# R284X.net
KiCad netlist of a schematic drawn in EAGLE
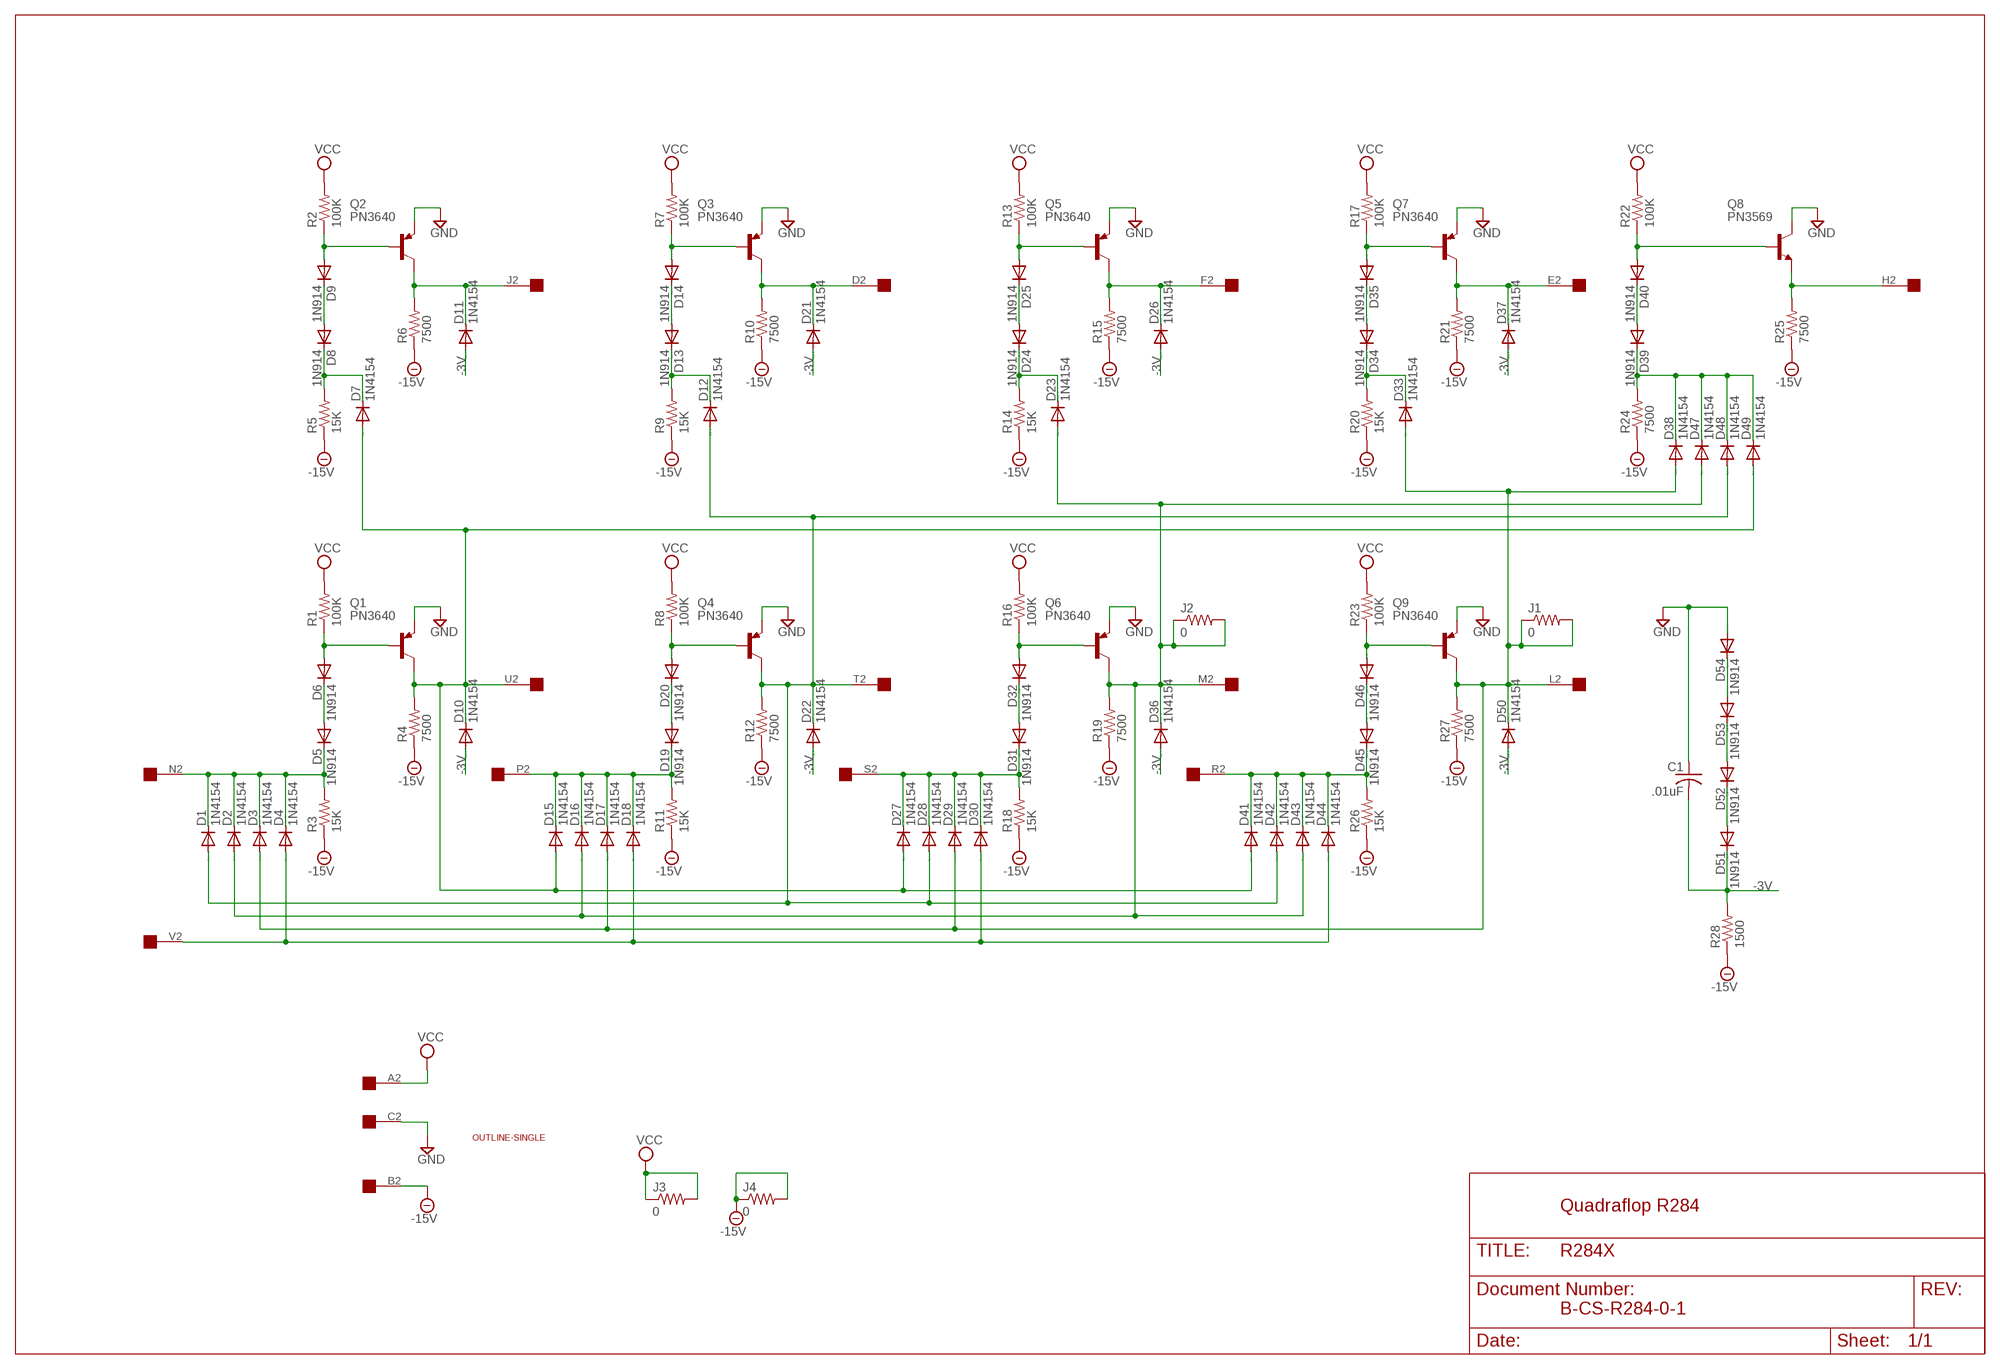
[diagram p0: schematic, sheet 1]

(export (version "E")
  (design (tool "Eeschema 10.0.6"))
  (components
    (comp (ref "C1")
      (value ".01uF")
      (footprint "eagle-import:C063-025X075")
      (libsource (lib "eagle-import") (part "C-US"))
    )
    (comp (ref "D1")
      (value "1N4154")
      (footprint "eagle-import:DO35-10")
      (libsource (lib "eagle-import") (part "DIODE-DO35-10"))
    )
    (comp (ref "D2")
      (value "1N4154")
      (footprint "eagle-import:DO35-10")
      (libsource (lib "eagle-import") (part "DIODE-DO35-10"))
    )
    (comp (ref "D3")
      (value "1N4154")
      (footprint "eagle-import:DO35-10")
      (libsource (lib "eagle-import") (part "DIODE-DO35-10"))
    )
    (comp (ref "D4")
      (value "1N4154")
      (footprint "eagle-import:DO35-10")
      (libsource (lib "eagle-import") (part "DIODE-DO35-10"))
    )
    (comp (ref "D5")
      (value "1N914")
      (footprint "eagle-import:DO35-10")
      (libsource (lib "eagle-import") (part "DIODE-DO35-10"))
    )
    (comp (ref "D6")
      (value "1N914")
      (footprint "eagle-import:DO35-10")
      (libsource (lib "eagle-import") (part "DIODE-DO35-10"))
    )
    (comp (ref "D7")
      (value "1N4154")
      (footprint "eagle-import:DO35-10")
      (libsource (lib "eagle-import") (part "DIODE-DO35-10"))
    )
    (comp (ref "D8")
      (value "1N914")
      (footprint "eagle-import:DO35-10")
      (libsource (lib "eagle-import") (part "DIODE-DO35-10"))
    )
    (comp (ref "D9")
      (value "1N914")
      (footprint "eagle-import:DO35-10")
      (libsource (lib "eagle-import") (part "DIODE-DO35-10"))
    )
    (comp (ref "D10")
      (value "1N4154")
      (footprint "eagle-import:DO35-10")
      (libsource (lib "eagle-import") (part "DIODE-DO35-10"))
    )
    (comp (ref "D11")
      (value "1N4154")
      (footprint "eagle-import:DO35-10")
      (libsource (lib "eagle-import") (part "DIODE-DO35-10"))
    )
    (comp (ref "D12")
      (value "1N4154")
      (footprint "eagle-import:DO35-10")
      (libsource (lib "eagle-import") (part "DIODE-DO35-10"))
    )
    (comp (ref "D13")
      (value "1N914")
      (footprint "eagle-import:DO35-10")
      (libsource (lib "eagle-import") (part "DIODE-DO35-10"))
    )
    (comp (ref "D14")
      (value "1N914")
      (footprint "eagle-import:DO35-10")
      (libsource (lib "eagle-import") (part "DIODE-DO35-10"))
    )
    (comp (ref "D15")
      (value "1N4154")
      (footprint "eagle-import:DO35-10")
      (libsource (lib "eagle-import") (part "DIODE-DO35-10"))
    )
    (comp (ref "D16")
      (value "1N4154")
      (footprint "eagle-import:DO35-10")
      (libsource (lib "eagle-import") (part "DIODE-DO35-10"))
    )
    (comp (ref "D17")
      (value "1N4154")
      (footprint "eagle-import:DO35-10")
      (libsource (lib "eagle-import") (part "DIODE-DO35-10"))
    )
    (comp (ref "D18")
      (value "1N4154")
      (footprint "eagle-import:DO35-10")
      (libsource (lib "eagle-import") (part "DIODE-DO35-10"))
    )
    (comp (ref "D19")
      (value "1N914")
      (footprint "eagle-import:DO35-10")
      (libsource (lib "eagle-import") (part "DIODE-DO35-10"))
    )
    (comp (ref "D20")
      (value "1N914")
      (footprint "eagle-import:DO35-10")
      (libsource (lib "eagle-import") (part "DIODE-DO35-10"))
    )
    (comp (ref "D21")
      (value "1N4154")
      (footprint "eagle-import:DO35-10")
      (libsource (lib "eagle-import") (part "DIODE-DO35-10"))
    )
    (comp (ref "D22")
      (value "1N4154")
      (footprint "eagle-import:DO35-10")
      (libsource (lib "eagle-import") (part "DIODE-DO35-10"))
    )
    (comp (ref "D23")
      (value "1N4154")
      (footprint "eagle-import:DO35-10")
      (libsource (lib "eagle-import") (part "DIODE-DO35-10"))
    )
    (comp (ref "D24")
      (value "1N914")
      (footprint "eagle-import:DO35-10")
      (libsource (lib "eagle-import") (part "DIODE-DO35-10"))
    )
    (comp (ref "D25")
      (value "1N914")
      (footprint "eagle-import:DO35-10")
      (libsource (lib "eagle-import") (part "DIODE-DO35-10"))
    )
    (comp (ref "D26")
      (value "1N4154")
      (footprint "eagle-import:DO35-10")
      (libsource (lib "eagle-import") (part "DIODE-DO35-10"))
    )
    (comp (ref "D27")
      (value "1N4154")
      (footprint "eagle-import:DO35-10")
      (libsource (lib "eagle-import") (part "DIODE-DO35-10"))
    )
    (comp (ref "D28")
      (value "1N4154")
      (footprint "eagle-import:DO35-10")
      (libsource (lib "eagle-import") (part "DIODE-DO35-10"))
    )
    (comp (ref "D29")
      (value "1N4154")
      (footprint "eagle-import:DO35-10")
      (libsource (lib "eagle-import") (part "DIODE-DO35-10"))
    )
    (comp (ref "D30")
      (value "1N4154")
      (footprint "eagle-import:DO35-10")
      (libsource (lib "eagle-import") (part "DIODE-DO35-10"))
    )
    (comp (ref "D31")
      (value "1N914")
      (footprint "eagle-import:DO35-10")
      (libsource (lib "eagle-import") (part "DIODE-DO35-10"))
    )
    (comp (ref "D32")
      (value "1N914")
      (footprint "eagle-import:DO35-10")
      (libsource (lib "eagle-import") (part "DIODE-DO35-10"))
    )
    (comp (ref "D33")
      (value "1N4154")
      (footprint "eagle-import:DO35-10")
      (libsource (lib "eagle-import") (part "DIODE-DO35-10"))
    )
    (comp (ref "D34")
      (value "1N914")
      (footprint "eagle-import:DO35-10")
      (libsource (lib "eagle-import") (part "DIODE-DO35-10"))
    )
    (comp (ref "D35")
      (value "1N914")
      (footprint "eagle-import:DO35-10")
      (libsource (lib "eagle-import") (part "DIODE-DO35-10"))
    )
    (comp (ref "D36")
      (value "1N4154")
      (footprint "eagle-import:DO35-10")
      (libsource (lib "eagle-import") (part "DIODE-DO35-10"))
    )
    (comp (ref "D37")
      (value "1N4154")
      (footprint "eagle-import:DO35-10")
      (libsource (lib "eagle-import") (part "DIODE-DO35-10"))
    )
    (comp (ref "D38")
      (value "1N4154")
      (footprint "eagle-import:DO35-10")
      (libsource (lib "eagle-import") (part "DIODE-DO35-10"))
    )
    (comp (ref "D39")
      (value "1N914")
      (footprint "eagle-import:DO35-10")
      (libsource (lib "eagle-import") (part "DIODE-DO35-10"))
    )
    (comp (ref "D40")
      (value "1N914")
      (footprint "eagle-import:DO35-10")
      (libsource (lib "eagle-import") (part "DIODE-DO35-10"))
    )
    (comp (ref "D41")
      (value "1N4154")
      (footprint "eagle-import:DO35-10")
      (libsource (lib "eagle-import") (part "DIODE-DO35-10"))
    )
    (comp (ref "D42")
      (value "1N4154")
      (footprint "eagle-import:DO35-10")
      (libsource (lib "eagle-import") (part "DIODE-DO35-10"))
    )
    (comp (ref "D43")
      (value "1N4154")
      (footprint "eagle-import:DO35-10")
      (libsource (lib "eagle-import") (part "DIODE-DO35-10"))
    )
    (comp (ref "D44")
      (value "1N4154")
      (footprint "eagle-import:DO35-10")
      (libsource (lib "eagle-import") (part "DIODE-DO35-10"))
    )
    (comp (ref "D45")
      (value "1N914")
      (footprint "eagle-import:DO35-10")
      (libsource (lib "eagle-import") (part "DIODE-DO35-10"))
    )
    (comp (ref "D46")
      (value "1N914")
      (footprint "eagle-import:DO35-10")
      (libsource (lib "eagle-import") (part "DIODE-DO35-10"))
    )
    (comp (ref "D47")
      (value "1N4154")
      (footprint "eagle-import:DO35-10")
      (libsource (lib "eagle-import") (part "DIODE-DO35-10"))
    )
    (comp (ref "D48")
      (value "1N4154")
      (footprint "eagle-import:DO35-10")
      (libsource (lib "eagle-import") (part "DIODE-DO35-10"))
    )
    (comp (ref "D49")
      (value "1N4154")
      (footprint "eagle-import:DO35-10")
      (libsource (lib "eagle-import") (part "DIODE-DO35-10"))
    )
    (comp (ref "D50")
      (value "1N4154")
      (footprint "eagle-import:DO35-10")
      (libsource (lib "eagle-import") (part "DIODE-DO35-10"))
    )
    (comp (ref "D51")
      (value "1N914")
      (footprint "eagle-import:DO35-10")
      (libsource (lib "eagle-import") (part "DIODE-DO35-10"))
    )
    (comp (ref "D52")
      (value "1N914")
      (footprint "eagle-import:DO35-10")
      (libsource (lib "eagle-import") (part "DIODE-DO35-10"))
    )
    (comp (ref "D53")
      (value "1N914")
      (footprint "eagle-import:DO35-10")
      (libsource (lib "eagle-import") (part "DIODE-DO35-10"))
    )
    (comp (ref "D54")
      (value "1N914")
      (footprint "eagle-import:DO35-10")
      (libsource (lib "eagle-import") (part "DIODE-DO35-10"))
    )
    (comp (ref "J1")
      (value "0")
      (footprint "eagle-import:0207_10")
      (libsource (lib "eagle-import") (part "R-US_0207/10"))
    )
    (comp (ref "J2")
      (value "0")
      (footprint "eagle-import:0207_10")
      (libsource (lib "eagle-import") (part "R-US_0207/10"))
    )
    (comp (ref "J3")
      (value "0")
      (footprint "eagle-import:0207_10")
      (libsource (lib "eagle-import") (part "R-US_0207/10"))
    )
    (comp (ref "J4")
      (value "0")
      (footprint "eagle-import:0207_10")
      (libsource (lib "eagle-import") (part "R-US_0207/10"))
    )
    (comp (ref "Q1")
      (value "PN3640")
      (footprint "eagle-import:TO5")
      (libsource (lib "eagle-import") (part "-PNP-TO5"))
    )
    (comp (ref "Q2")
      (value "PN3640")
      (footprint "eagle-import:TO5")
      (libsource (lib "eagle-import") (part "-PNP-TO5"))
    )
    (comp (ref "Q3")
      (value "PN3640")
      (footprint "eagle-import:TO5")
      (libsource (lib "eagle-import") (part "-PNP-TO5"))
    )
    (comp (ref "Q4")
      (value "PN3640")
      (footprint "eagle-import:TO5")
      (libsource (lib "eagle-import") (part "-PNP-TO5"))
    )
    (comp (ref "Q5")
      (value "PN3640")
      (footprint "eagle-import:TO5")
      (libsource (lib "eagle-import") (part "-PNP-TO5"))
    )
    (comp (ref "Q6")
      (value "PN3640")
      (footprint "eagle-import:TO5")
      (libsource (lib "eagle-import") (part "-PNP-TO5"))
    )
    (comp (ref "Q7")
      (value "PN3640")
      (footprint "eagle-import:TO5")
      (libsource (lib "eagle-import") (part "-PNP-TO5"))
    )
    (comp (ref "Q8")
      (value "PN3569")
      (footprint "eagle-import:TO5")
      (libsource (lib "eagle-import") (part "-NPN-TO5"))
    )
    (comp (ref "Q9")
      (value "PN3640")
      (footprint "eagle-import:TO5")
      (libsource (lib "eagle-import") (part "-PNP-TO5"))
    )
    (comp (ref "R1")
      (value "100K")
      (footprint "eagle-import:0207_10")
      (libsource (lib "eagle-import") (part "R-US_0207/10"))
    )
    (comp (ref "R2")
      (value "100K")
      (footprint "eagle-import:0207_10")
      (libsource (lib "eagle-import") (part "R-US_0207/10"))
    )
    (comp (ref "R3")
      (value "15K")
      (footprint "eagle-import:0207_10")
      (libsource (lib "eagle-import") (part "R-US_0207/10"))
    )
    (comp (ref "R4")
      (value "7500")
      (footprint "eagle-import:0207_10")
      (libsource (lib "eagle-import") (part "R-US_0207/10"))
    )
    (comp (ref "R5")
      (value "15K")
      (footprint "eagle-import:0207_10")
      (libsource (lib "eagle-import") (part "R-US_0207/10"))
    )
    (comp (ref "R6")
      (value "7500")
      (footprint "eagle-import:0207_10")
      (libsource (lib "eagle-import") (part "R-US_0207/10"))
    )
    (comp (ref "R7")
      (value "100K")
      (footprint "eagle-import:0207_10")
      (libsource (lib "eagle-import") (part "R-US_0207/10"))
    )
    (comp (ref "R8")
      (value "100K")
      (footprint "eagle-import:0207_10")
      (libsource (lib "eagle-import") (part "R-US_0207/10"))
    )
    (comp (ref "R9")
      (value "15K")
      (footprint "eagle-import:0207_10")
      (libsource (lib "eagle-import") (part "R-US_0207/10"))
    )
    (comp (ref "R10")
      (value "7500")
      (footprint "eagle-import:0207_10")
      (libsource (lib "eagle-import") (part "R-US_0207/10"))
    )
    (comp (ref "R11")
      (value "15K")
      (footprint "eagle-import:0207_10")
      (libsource (lib "eagle-import") (part "R-US_0207/10"))
    )
    (comp (ref "R12")
      (value "7500")
      (footprint "eagle-import:0207_10")
      (libsource (lib "eagle-import") (part "R-US_0207/10"))
    )
    (comp (ref "R13")
      (value "100K")
      (footprint "eagle-import:0207_10")
      (libsource (lib "eagle-import") (part "R-US_0207/10"))
    )
    (comp (ref "R14")
      (value "15K")
      (footprint "eagle-import:0207_10")
      (libsource (lib "eagle-import") (part "R-US_0207/10"))
    )
    (comp (ref "R15")
      (value "7500")
      (footprint "eagle-import:0207_10")
      (libsource (lib "eagle-import") (part "R-US_0207/10"))
    )
    (comp (ref "R16")
      (value "100K")
      (footprint "eagle-import:0207_10")
      (libsource (lib "eagle-import") (part "R-US_0207/10"))
    )
    (comp (ref "R17")
      (value "100K")
      (footprint "eagle-import:0207_10")
      (libsource (lib "eagle-import") (part "R-US_0207/10"))
    )
    (comp (ref "R18")
      (value "15K")
      (footprint "eagle-import:0207_10")
      (libsource (lib "eagle-import") (part "R-US_0207/10"))
    )
    (comp (ref "R19")
      (value "7500")
      (footprint "eagle-import:0207_10")
      (libsource (lib "eagle-import") (part "R-US_0207/10"))
    )
    (comp (ref "R20")
      (value "15K")
      (footprint "eagle-import:0207_10")
      (libsource (lib "eagle-import") (part "R-US_0207/10"))
    )
    (comp (ref "R21")
      (value "7500")
      (footprint "eagle-import:0207_10")
      (libsource (lib "eagle-import") (part "R-US_0207/10"))
    )
    (comp (ref "R22")
      (value "100K")
      (footprint "eagle-import:0207_10")
      (libsource (lib "eagle-import") (part "R-US_0207/10"))
    )
    (comp (ref "R23")
      (value "100K")
      (footprint "eagle-import:0207_10")
      (libsource (lib "eagle-import") (part "R-US_0207/10"))
    )
    (comp (ref "R24")
      (value "7500")
      (footprint "eagle-import:0207_10")
      (libsource (lib "eagle-import") (part "R-US_0207/10"))
    )
    (comp (ref "R25")
      (value "7500")
      (footprint "eagle-import:0207_10")
      (libsource (lib "eagle-import") (part "R-US_0207/10"))
    )
    (comp (ref "R26")
      (value "15K")
      (footprint "eagle-import:0207_10")
      (libsource (lib "eagle-import") (part "R-US_0207/10"))
    )
    (comp (ref "R27")
      (value "7500")
      (footprint "eagle-import:0207_10")
      (libsource (lib "eagle-import") (part "R-US_0207/10"))
    )
    (comp (ref "R28")
      (value "1500")
      (footprint "eagle-import:0207_10")
      (libsource (lib "eagle-import") (part "R-US_0207/10"))
    )
    (comp (ref "U$1")
      (value "OUTLINE-SINGLE")
      (footprint "eagle-import:SINGLE")
      (libsource (lib "eagle-import") (part "OUTLINE-SINGLE"))
    )
    (comp (ref "U$2")
      (value "EDGE-1")
      (footprint "eagle-import:EDGE-CON1")
      (libsource (lib "eagle-import") (part "EDGE-1"))
    )
  )
  (nets
    (net (code "1") (name "-15V") (class "Default")
      (node (ref "J4") (pin "1") (pinfunction "1_1") (pintype "passive"))
      (node (ref "J4") (pin "2") (pinfunction "2_2") (pintype "passive"))
      (node (ref "R10") (pin "1") (pinfunction "1_1") (pintype "passive"))
      (node (ref "R11") (pin "1") (pinfunction "1_1") (pintype "passive"))
      (node (ref "R12") (pin "1") (pinfunction "1_1") (pintype "passive"))
      (node (ref "R14") (pin "1") (pinfunction "1_1") (pintype "passive"))
      (node (ref "R15") (pin "1") (pinfunction "1_1") (pintype "passive"))
      (node (ref "R18") (pin "1") (pinfunction "1_1") (pintype "passive"))
      (node (ref "R19") (pin "1") (pinfunction "1_1") (pintype "passive"))
      (node (ref "R20") (pin "1") (pinfunction "1_1") (pintype "passive"))
      (node (ref "R21") (pin "1") (pinfunction "1_1") (pintype "passive"))
      (node (ref "R24") (pin "1") (pinfunction "1_1") (pintype "passive"))
      (node (ref "R25") (pin "1") (pinfunction "1_1") (pintype "passive"))
      (node (ref "R26") (pin "1") (pinfunction "1_1") (pintype "passive"))
      (node (ref "R27") (pin "1") (pinfunction "1_1") (pintype "passive"))
      (node (ref "R28") (pin "1") (pinfunction "1_1") (pintype "passive"))
      (node (ref "R3") (pin "1") (pinfunction "1_1") (pintype "passive"))
      (node (ref "R4") (pin "1") (pinfunction "1_1") (pintype "passive"))
      (node (ref "R5") (pin "1") (pinfunction "1_1") (pintype "passive"))
      (node (ref "R6") (pin "1") (pinfunction "1_1") (pintype "passive"))
      (node (ref "R9") (pin "1") (pinfunction "1_1") (pintype "passive"))
      (node (ref "U$2") (pin "B2") (pinfunction "1_B2") (pintype "bidirectional"))
    )
    (net (code "2") (name "/-3V") (class "Default")
      (node (ref "C1") (pin "2") (pinfunction "2_2") (pintype "passive"))
      (node (ref "D10") (pin "A") (pinfunction "A_A") (pintype "passive"))
      (node (ref "D11") (pin "A") (pinfunction "A_A") (pintype "passive"))
      (node (ref "D21") (pin "A") (pinfunction "A_A") (pintype "passive"))
      (node (ref "D22") (pin "A") (pinfunction "A_A") (pintype "passive"))
      (node (ref "D26") (pin "A") (pinfunction "A_A") (pintype "passive"))
      (node (ref "D36") (pin "A") (pinfunction "A_A") (pintype "passive"))
      (node (ref "D37") (pin "A") (pinfunction "A_A") (pintype "passive"))
      (node (ref "D50") (pin "A") (pinfunction "A_A") (pintype "passive"))
      (node (ref "D51") (pin "C") (pinfunction "C_C") (pintype "passive"))
      (node (ref "R28") (pin "2") (pinfunction "2_2") (pintype "passive"))
    )
    (net (code "3") (name "GND") (class "Default")
      (node (ref "C1") (pin "1") (pinfunction "1_1") (pintype "passive"))
      (node (ref "D54") (pin "A") (pinfunction "A_A") (pintype "passive"))
      (node (ref "Q1") (pin "1") (pinfunction "E_1") (pintype "passive"))
      (node (ref "Q2") (pin "1") (pinfunction "E_1") (pintype "passive"))
      (node (ref "Q3") (pin "1") (pinfunction "E_1") (pintype "passive"))
      (node (ref "Q4") (pin "1") (pinfunction "E_1") (pintype "passive"))
      (node (ref "Q5") (pin "1") (pinfunction "E_1") (pintype "passive"))
      (node (ref "Q6") (pin "1") (pinfunction "E_1") (pintype "passive"))
      (node (ref "Q7") (pin "1") (pinfunction "E_1") (pintype "passive"))
      (node (ref "Q8") (pin "3") (pinfunction "C_3") (pintype "passive"))
      (node (ref "Q9") (pin "1") (pinfunction "E_1") (pintype "passive"))
      (node (ref "U$2") (pin "C2") (pinfunction "1_C2") (pintype "bidirectional"))
    )
    (net (code "4") (name "Net-(D5-PadA)") (class "Default")
      (node (ref "D5") (pin "A") (pinfunction "A_A") (pintype "passive"))
      (node (ref "D6") (pin "C") (pinfunction "C_C") (pintype "passive"))
    )
    (net (code "5") (name "Net-(D7-PadC)") (class "Default")
      (node (ref "D7") (pin "C") (pinfunction "C_C") (pintype "passive"))
      (node (ref "D8") (pin "C") (pinfunction "C_C") (pintype "passive"))
      (node (ref "R5") (pin "2") (pinfunction "2_2") (pintype "passive"))
    )
    (net (code "6") (name "Net-(D8-PadA)") (class "Default")
      (node (ref "D8") (pin "A") (pinfunction "A_A") (pintype "passive"))
      (node (ref "D9") (pin "C") (pinfunction "C_C") (pintype "passive"))
    )
    (net (code "7") (name "Net-(D12-PadC)") (class "Default")
      (node (ref "D12") (pin "C") (pinfunction "C_C") (pintype "passive"))
      (node (ref "D13") (pin "C") (pinfunction "C_C") (pintype "passive"))
      (node (ref "R9") (pin "2") (pinfunction "2_2") (pintype "passive"))
    )
    (net (code "8") (name "Net-(D13-PadA)") (class "Default")
      (node (ref "D13") (pin "A") (pinfunction "A_A") (pintype "passive"))
      (node (ref "D14") (pin "C") (pinfunction "C_C") (pintype "passive"))
    )
    (net (code "9") (name "Net-(D19-PadA)") (class "Default")
      (node (ref "D19") (pin "A") (pinfunction "A_A") (pintype "passive"))
      (node (ref "D20") (pin "C") (pinfunction "C_C") (pintype "passive"))
    )
    (net (code "10") (name "Net-(D23-PadC)") (class "Default")
      (node (ref "D23") (pin "C") (pinfunction "C_C") (pintype "passive"))
      (node (ref "D24") (pin "C") (pinfunction "C_C") (pintype "passive"))
      (node (ref "R14") (pin "2") (pinfunction "2_2") (pintype "passive"))
    )
    (net (code "11") (name "Net-(D24-PadA)") (class "Default")
      (node (ref "D24") (pin "A") (pinfunction "A_A") (pintype "passive"))
      (node (ref "D25") (pin "C") (pinfunction "C_C") (pintype "passive"))
    )
    (net (code "12") (name "Net-(D31-PadA)") (class "Default")
      (node (ref "D31") (pin "A") (pinfunction "A_A") (pintype "passive"))
      (node (ref "D32") (pin "C") (pinfunction "C_C") (pintype "passive"))
    )
    (net (code "13") (name "Net-(D33-PadC)") (class "Default")
      (node (ref "D33") (pin "C") (pinfunction "C_C") (pintype "passive"))
      (node (ref "D34") (pin "C") (pinfunction "C_C") (pintype "passive"))
      (node (ref "R20") (pin "2") (pinfunction "2_2") (pintype "passive"))
    )
    (net (code "14") (name "Net-(D34-PadA)") (class "Default")
      (node (ref "D34") (pin "A") (pinfunction "A_A") (pintype "passive"))
      (node (ref "D35") (pin "C") (pinfunction "C_C") (pintype "passive"))
    )
    (net (code "15") (name "Net-(D38-PadC)") (class "Default")
      (node (ref "D38") (pin "C") (pinfunction "C_C") (pintype "passive"))
      (node (ref "D39") (pin "C") (pinfunction "C_C") (pintype "passive"))
      (node (ref "D47") (pin "C") (pinfunction "C_C") (pintype "passive"))
      (node (ref "D48") (pin "C") (pinfunction "C_C") (pintype "passive"))
      (node (ref "D49") (pin "C") (pinfunction "C_C") (pintype "passive"))
      (node (ref "R24") (pin "2") (pinfunction "2_2") (pintype "passive"))
    )
    (net (code "16") (name "Net-(D39-PadA)") (class "Default")
      (node (ref "D39") (pin "A") (pinfunction "A_A") (pintype "passive"))
      (node (ref "D40") (pin "C") (pinfunction "C_C") (pintype "passive"))
    )
    (net (code "17") (name "Net-(D45-PadA)") (class "Default")
      (node (ref "D45") (pin "A") (pinfunction "A_A") (pintype "passive"))
      (node (ref "D46") (pin "C") (pinfunction "C_C") (pintype "passive"))
    )
    (net (code "18") (name "Net-(D51-PadA)") (class "Default")
      (node (ref "D51") (pin "A") (pinfunction "A_A") (pintype "passive"))
      (node (ref "D52") (pin "C") (pinfunction "C_C") (pintype "passive"))
    )
    (net (code "19") (name "Net-(D52-PadA)") (class "Default")
      (node (ref "D52") (pin "A") (pinfunction "A_A") (pintype "passive"))
      (node (ref "D53") (pin "C") (pinfunction "C_C") (pintype "passive"))
    )
    (net (code "20") (name "Net-(D53-PadA)") (class "Default")
      (node (ref "D53") (pin "A") (pinfunction "A_A") (pintype "passive"))
      (node (ref "D54") (pin "C") (pinfunction "C_C") (pintype "passive"))
    )
    (net (code "21") (name "Net-(Q1-B)") (class "Default")
      (node (ref "D6") (pin "A") (pinfunction "A_A") (pintype "passive"))
      (node (ref "Q1") (pin "2") (pinfunction "B_2") (pintype "passive"))
      (node (ref "R1") (pin "1") (pinfunction "1_1") (pintype "passive"))
    )
    (net (code "22") (name "Net-(Q1-C)") (class "Default")
      (node (ref "D10") (pin "C") (pinfunction "C_C") (pintype "passive"))
      (node (ref "D15") (pin "A") (pinfunction "A_A") (pintype "passive"))
      (node (ref "D27") (pin "A") (pinfunction "A_A") (pintype "passive"))
      (node (ref "D41") (pin "A") (pinfunction "A_A") (pintype "passive"))
      (node (ref "D49") (pin "A") (pinfunction "A_A") (pintype "passive"))
      (node (ref "D7") (pin "A") (pinfunction "A_A") (pintype "passive"))
      (node (ref "Q1") (pin "3") (pinfunction "C_3") (pintype "passive"))
      (node (ref "R4") (pin "2") (pinfunction "2_2") (pintype "passive"))
      (node (ref "U$2") (pin "U2") (pinfunction "1_U2") (pintype "bidirectional"))
    )
    (net (code "23") (name "Net-(Q2-B)") (class "Default")
      (node (ref "D9") (pin "A") (pinfunction "A_A") (pintype "passive"))
      (node (ref "Q2") (pin "2") (pinfunction "B_2") (pintype "passive"))
      (node (ref "R2") (pin "1") (pinfunction "1_1") (pintype "passive"))
    )
    (net (code "24") (name "Net-(Q2-C)") (class "Default")
      (node (ref "D11") (pin "C") (pinfunction "C_C") (pintype "passive"))
      (node (ref "Q2") (pin "3") (pinfunction "C_3") (pintype "passive"))
      (node (ref "R6") (pin "2") (pinfunction "2_2") (pintype "passive"))
      (node (ref "U$2") (pin "J2") (pinfunction "1_J2") (pintype "bidirectional"))
    )
    (net (code "25") (name "Net-(Q3-B)") (class "Default")
      (node (ref "D14") (pin "A") (pinfunction "A_A") (pintype "passive"))
      (node (ref "Q3") (pin "2") (pinfunction "B_2") (pintype "passive"))
      (node (ref "R7") (pin "1") (pinfunction "1_1") (pintype "passive"))
    )
    (net (code "26") (name "Net-(Q3-C)") (class "Default")
      (node (ref "D21") (pin "C") (pinfunction "C_C") (pintype "passive"))
      (node (ref "Q3") (pin "3") (pinfunction "C_3") (pintype "passive"))
      (node (ref "R10") (pin "2") (pinfunction "2_2") (pintype "passive"))
      (node (ref "U$2") (pin "D2") (pinfunction "1_D2") (pintype "bidirectional"))
    )
    (net (code "27") (name "Net-(Q4-B)") (class "Default")
      (node (ref "D20") (pin "A") (pinfunction "A_A") (pintype "passive"))
      (node (ref "Q4") (pin "2") (pinfunction "B_2") (pintype "passive"))
      (node (ref "R8") (pin "1") (pinfunction "1_1") (pintype "passive"))
    )
    (net (code "28") (name "Net-(Q4-C)") (class "Default")
      (node (ref "D1") (pin "A") (pinfunction "A_A") (pintype "passive"))
      (node (ref "D12") (pin "A") (pinfunction "A_A") (pintype "passive"))
      (node (ref "D22") (pin "C") (pinfunction "C_C") (pintype "passive"))
      (node (ref "D28") (pin "A") (pinfunction "A_A") (pintype "passive"))
      (node (ref "D42") (pin "A") (pinfunction "A_A") (pintype "passive"))
      (node (ref "D48") (pin "A") (pinfunction "A_A") (pintype "passive"))
      (node (ref "Q4") (pin "3") (pinfunction "C_3") (pintype "passive"))
      (node (ref "R12") (pin "2") (pinfunction "2_2") (pintype "passive"))
      (node (ref "U$2") (pin "T2") (pinfunction "1_T2") (pintype "bidirectional"))
    )
    (net (code "29") (name "Net-(Q5-B)") (class "Default")
      (node (ref "D25") (pin "A") (pinfunction "A_A") (pintype "passive"))
      (node (ref "Q5") (pin "2") (pinfunction "B_2") (pintype "passive"))
      (node (ref "R13") (pin "1") (pinfunction "1_1") (pintype "passive"))
    )
    (net (code "30") (name "Net-(Q5-C)") (class "Default")
      (node (ref "D26") (pin "C") (pinfunction "C_C") (pintype "passive"))
      (node (ref "Q5") (pin "3") (pinfunction "C_3") (pintype "passive"))
      (node (ref "R15") (pin "2") (pinfunction "2_2") (pintype "passive"))
      (node (ref "U$2") (pin "F2") (pinfunction "1_F2") (pintype "bidirectional"))
    )
    (net (code "31") (name "Net-(Q6-B)") (class "Default")
      (node (ref "D32") (pin "A") (pinfunction "A_A") (pintype "passive"))
      (node (ref "Q6") (pin "2") (pinfunction "B_2") (pintype "passive"))
      (node (ref "R16") (pin "1") (pinfunction "1_1") (pintype "passive"))
    )
    (net (code "32") (name "Net-(Q6-C)") (class "Default")
      (node (ref "D16") (pin "A") (pinfunction "A_A") (pintype "passive"))
      (node (ref "D2") (pin "A") (pinfunction "A_A") (pintype "passive"))
      (node (ref "D23") (pin "A") (pinfunction "A_A") (pintype "passive"))
      (node (ref "D36") (pin "C") (pinfunction "C_C") (pintype "passive"))
      (node (ref "D43") (pin "A") (pinfunction "A_A") (pintype "passive"))
      (node (ref "D47") (pin "A") (pinfunction "A_A") (pintype "passive"))
      (node (ref "J2") (pin "1") (pinfunction "1_1") (pintype "passive"))
      (node (ref "J2") (pin "2") (pinfunction "2_2") (pintype "passive"))
      (node (ref "Q6") (pin "3") (pinfunction "C_3") (pintype "passive"))
      (node (ref "R19") (pin "2") (pinfunction "2_2") (pintype "passive"))
      (node (ref "U$2") (pin "M2") (pinfunction "1_M2") (pintype "bidirectional"))
    )
    (net (code "33") (name "Net-(Q7-B)") (class "Default")
      (node (ref "D35") (pin "A") (pinfunction "A_A") (pintype "passive"))
      (node (ref "Q7") (pin "2") (pinfunction "B_2") (pintype "passive"))
      (node (ref "R17") (pin "1") (pinfunction "1_1") (pintype "passive"))
    )
    (net (code "34") (name "Net-(Q7-C)") (class "Default")
      (node (ref "D37") (pin "C") (pinfunction "C_C") (pintype "passive"))
      (node (ref "Q7") (pin "3") (pinfunction "C_3") (pintype "passive"))
      (node (ref "R21") (pin "2") (pinfunction "2_2") (pintype "passive"))
      (node (ref "U$2") (pin "E2") (pinfunction "1_E2") (pintype "bidirectional"))
    )
    (net (code "35") (name "Net-(Q8-B)") (class "Default")
      (node (ref "D40") (pin "A") (pinfunction "A_A") (pintype "passive"))
      (node (ref "Q8") (pin "2") (pinfunction "B_2") (pintype "passive"))
      (node (ref "R22") (pin "1") (pinfunction "1_1") (pintype "passive"))
    )
    (net (code "36") (name "Net-(Q8-E)") (class "Default")
      (node (ref "Q8") (pin "1") (pinfunction "E_1") (pintype "passive"))
      (node (ref "R25") (pin "2") (pinfunction "2_2") (pintype "passive"))
      (node (ref "U$2") (pin "H2") (pinfunction "1_H2") (pintype "bidirectional"))
    )
    (net (code "37") (name "Net-(Q9-B)") (class "Default")
      (node (ref "D46") (pin "A") (pinfunction "A_A") (pintype "passive"))
      (node (ref "Q9") (pin "2") (pinfunction "B_2") (pintype "passive"))
      (node (ref "R23") (pin "1") (pinfunction "1_1") (pintype "passive"))
    )
    (net (code "38") (name "Net-(Q9-C)") (class "Default")
      (node (ref "D17") (pin "A") (pinfunction "A_A") (pintype "passive"))
      (node (ref "D29") (pin "A") (pinfunction "A_A") (pintype "passive"))
      (node (ref "D3") (pin "A") (pinfunction "A_A") (pintype "passive"))
      (node (ref "D33") (pin "A") (pinfunction "A_A") (pintype "passive"))
      (node (ref "D38") (pin "A") (pinfunction "A_A") (pintype "passive"))
      (node (ref "D50") (pin "C") (pinfunction "C_C") (pintype "passive"))
      (node (ref "J1") (pin "1") (pinfunction "1_1") (pintype "passive"))
      (node (ref "J1") (pin "2") (pinfunction "2_2") (pintype "passive"))
      (node (ref "Q9") (pin "3") (pinfunction "C_3") (pintype "passive"))
      (node (ref "R27") (pin "2") (pinfunction "2_2") (pintype "passive"))
      (node (ref "U$2") (pin "L2") (pinfunction "1_L2") (pintype "bidirectional"))
    )
    (net (code "39") (name "Net-(U$2L-1)") (class "Default")
      (node (ref "D1") (pin "C") (pinfunction "C_C") (pintype "passive"))
      (node (ref "D2") (pin "C") (pinfunction "C_C") (pintype "passive"))
      (node (ref "D3") (pin "C") (pinfunction "C_C") (pintype "passive"))
      (node (ref "D4") (pin "C") (pinfunction "C_C") (pintype "passive"))
      (node (ref "D5") (pin "C") (pinfunction "C_C") (pintype "passive"))
      (node (ref "R3") (pin "2") (pinfunction "2_2") (pintype "passive"))
      (node (ref "U$2") (pin "N2") (pinfunction "1_N2") (pintype "bidirectional"))
    )
    (net (code "40") (name "Net-(U$2M-1)") (class "Default")
      (node (ref "D15") (pin "C") (pinfunction "C_C") (pintype "passive"))
      (node (ref "D16") (pin "C") (pinfunction "C_C") (pintype "passive"))
      (node (ref "D17") (pin "C") (pinfunction "C_C") (pintype "passive"))
      (node (ref "D18") (pin "C") (pinfunction "C_C") (pintype "passive"))
      (node (ref "D19") (pin "C") (pinfunction "C_C") (pintype "passive"))
      (node (ref "R11") (pin "2") (pinfunction "2_2") (pintype "passive"))
      (node (ref "U$2") (pin "P2") (pinfunction "1_P2") (pintype "bidirectional"))
    )
    (net (code "41") (name "Net-(U$2N-1)") (class "Default")
      (node (ref "D41") (pin "C") (pinfunction "C_C") (pintype "passive"))
      (node (ref "D42") (pin "C") (pinfunction "C_C") (pintype "passive"))
      (node (ref "D43") (pin "C") (pinfunction "C_C") (pintype "passive"))
      (node (ref "D44") (pin "C") (pinfunction "C_C") (pintype "passive"))
      (node (ref "D45") (pin "C") (pinfunction "C_C") (pintype "passive"))
      (node (ref "R26") (pin "2") (pinfunction "2_2") (pintype "passive"))
      (node (ref "U$2") (pin "R2") (pinfunction "1_R2") (pintype "bidirectional"))
    )
    (net (code "42") (name "Net-(U$2O-1)") (class "Default")
      (node (ref "D27") (pin "C") (pinfunction "C_C") (pintype "passive"))
      (node (ref "D28") (pin "C") (pinfunction "C_C") (pintype "passive"))
      (node (ref "D29") (pin "C") (pinfunction "C_C") (pintype "passive"))
      (node (ref "D30") (pin "C") (pinfunction "C_C") (pintype "passive"))
      (node (ref "D31") (pin "C") (pinfunction "C_C") (pintype "passive"))
      (node (ref "R18") (pin "2") (pinfunction "2_2") (pintype "passive"))
      (node (ref "U$2") (pin "S2") (pinfunction "1_S2") (pintype "bidirectional"))
    )
    (net (code "43") (name "Net-(U$2R-1)") (class "Default")
      (node (ref "D18") (pin "A") (pinfunction "A_A") (pintype "passive"))
      (node (ref "D30") (pin "A") (pinfunction "A_A") (pintype "passive"))
      (node (ref "D4") (pin "A") (pinfunction "A_A") (pintype "passive"))
      (node (ref "D44") (pin "A") (pinfunction "A_A") (pintype "passive"))
      (node (ref "U$2") (pin "V2") (pinfunction "1_V2") (pintype "bidirectional"))
    )
    (net (code "44") (name "VCC") (class "Default")
      (node (ref "J3") (pin "1") (pinfunction "1_1") (pintype "passive"))
      (node (ref "J3") (pin "2") (pinfunction "2_2") (pintype "passive"))
      (node (ref "R1") (pin "2") (pinfunction "2_2") (pintype "passive"))
      (node (ref "R13") (pin "2") (pinfunction "2_2") (pintype "passive"))
      (node (ref "R16") (pin "2") (pinfunction "2_2") (pintype "passive"))
      (node (ref "R17") (pin "2") (pinfunction "2_2") (pintype "passive"))
      (node (ref "R2") (pin "2") (pinfunction "2_2") (pintype "passive"))
      (node (ref "R22") (pin "2") (pinfunction "2_2") (pintype "passive"))
      (node (ref "R23") (pin "2") (pinfunction "2_2") (pintype "passive"))
      (node (ref "R7") (pin "2") (pinfunction "2_2") (pintype "passive"))
      (node (ref "R8") (pin "2") (pinfunction "2_2") (pintype "passive"))
      (node (ref "U$2") (pin "A2") (pinfunction "1_A2") (pintype "bidirectional"))
    )
  )
)
